# BaseNode.net
KiCad netlist of a schematic drawn in Altium Designer
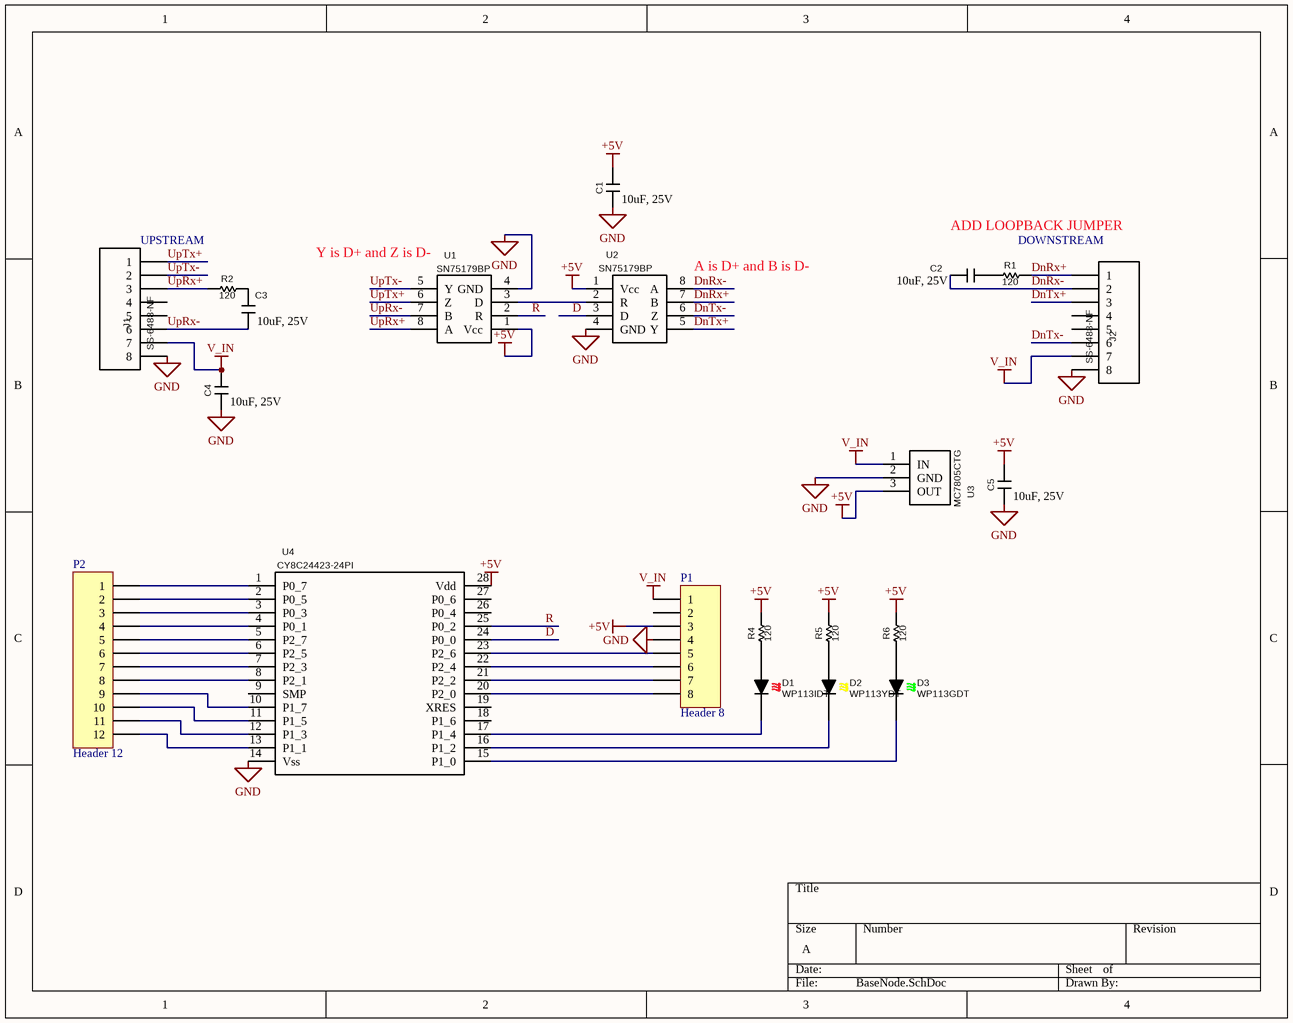
[diagram p0: BaseNode.SchDoc]

(export (version "E")
  (design (tool "Eeschema 10.0.6"))
  (components
    (comp (ref "C1")
      (value "10uF, 25V")
      (footprint "whong:Capacitor TH 0.2")
      (description "Capacitor")
      (fields (field (name "MANUFACTURER") "TDK Corporation"))
      (libsource (lib "whong") (part "Capacitor"))
    )
    (comp (ref "C2")
      (value "10uF, 25V")
      (footprint "whong:Capacitor TH 0.2")
      (description "Capacitor")
      (fields (field (name "MANUFACTURER") "TDK Corporation"))
      (libsource (lib "whong") (part "Capacitor"))
    )
    (comp (ref "C3")
      (value "10uF, 25V")
      (footprint "whong:Capacitor TH 0.2")
      (description "Capacitor")
      (fields (field (name "MANUFACTURER") "TDK Corporation"))
      (libsource (lib "whong") (part "Capacitor"))
    )
    (comp (ref "C4")
      (value "10uF, 25V")
      (footprint "whong:Capacitor TH 0.2")
      (description "Capacitor")
      (fields (field (name "MANUFACTURER") "TDK Corporation"))
      (libsource (lib "whong") (part "Capacitor"))
    )
    (comp (ref "C5")
      (value "10uF, 25V")
      (footprint "whong:Capacitor TH 0.2")
      (description "Capacitor")
      (fields (field (name "MANUFACTURER") "TDK Corporation"))
      (libsource (lib "whong") (part "Capacitor"))
    )
    (comp (ref "D1")
      (value "WP113IDT")
      (footprint "whong:LED 100mil")
      (description "LED RECT 2X5MM 625NM RED DIFF")
      (fields (field (name "MANUFACTURER") "Kingbright Corp") (field (name "MANUFACTURERPN") "WP113IDT"))
      (libsource (lib "whong") (part "WP113IDT"))
    )
    (comp (ref "D2")
      (value "WP113YDT")
      (footprint "whong:LED 100mil")
      (description "LED RECT 2X5MM 588NM YLW DIFF")
      (fields (field (name "MANUFACTURER") "Kingbright Corp") (field (name "MANUFACTURERPN") "WP113YDT"))
      (libsource (lib "whong") (part "WP113YDT"))
    )
    (comp (ref "D3")
      (value "WP113GDT")
      (footprint "whong:LED 100mil")
      (description "LED RECT 2X5MM 568NM GRN DIFF")
      (fields (field (name "MANUFACTURER") "Kingbright Corp") (field (name "MANUFACTURERPN") "WP113GDT"))
      (libsource (lib "whong") (part "WP113GDT"))
    )
    (comp (ref "J1")
      (value "SS-6488-NF")
      (footprint "whong:SS-6488-NF")
      (description "CONN 8-8 MOD JACK")
      (fields (field (name "MANUFACTURER") "Stewart Connector"))
      (libsource (lib "") (part "SS-6488-NF_1"))
    )
    (comp (ref "J2")
      (value "SS-6488-NF")
      (footprint "whong:SS-6488-NF")
      (description "CONN 8-8 MOD JACK")
      (fields (field (name "MANUFACTURER") "Stewart Connector"))
      (libsource (lib "whong") (part "SS-6488-NF"))
    )
    (comp (ref "P1")
      (value "Header 8")
      (footprint "HDR1X8")
      (description "Header, 8-Pin")
      (fields (field (name "PUBLISHER") "Altium Limited"))
      (libsource (lib "Miscellaneous Connectors") (part "Header 8"))
    )
    (comp (ref "P2")
      (value "Header 12")
      (footprint "HDR1X12")
      (description "Header, 12-Pin")
      (fields (field (name "PUBLISHER") "Altium Limited"))
      (libsource (lib "Miscellaneous Connectors") (part "Header 12"))
    )
    (comp (ref "R1")
      (value "120")
      (footprint "whong:Resistor Axial 100mil")
      (description "Resistor")
      (fields (field (name "MANUFACTURER") "Stackpole Electronics Inc") (field (name "TOLERANCE") "5%"))
      (libsource (lib "whong") (part "Resistor"))
    )
    (comp (ref "R2")
      (value "120")
      (footprint "whong:Resistor Axial 100mil")
      (description "Resistor")
      (fields (field (name "MANUFACTURER") "Stackpole Electronics Inc") (field (name "TOLERANCE") "5%"))
      (libsource (lib "whong") (part "Resistor"))
    )
    (comp (ref "R4")
      (value "120")
      (footprint "whong:Resistor Axial 100mil")
      (description "Resistor")
      (fields (field (name "MANUFACTURER") "Stackpole Electronics Inc") (field (name "TOLERANCE") "5%"))
      (libsource (lib "whong") (part "Resistor"))
    )
    (comp (ref "R5")
      (value "120")
      (footprint "whong:Resistor Axial 100mil")
      (description "Resistor")
      (fields (field (name "MANUFACTURER") "Stackpole Electronics Inc") (field (name "TOLERANCE") "5%"))
      (libsource (lib "whong") (part "Resistor"))
    )
    (comp (ref "R6")
      (value "120")
      (footprint "whong:Resistor Axial 100mil")
      (description "Resistor")
      (fields (field (name "MANUFACTURER") "Stackpole Electronics Inc") (field (name "TOLERANCE") "5%"))
      (libsource (lib "whong") (part "Resistor"))
    )
    (comp (ref "U1")
      (value "SN75179BP")
      (footprint "dip8")
      (description "IC DIFF DRIVER/RECPAIR 8-DIP")
      (fields (field (name "MANUFACTURER") "Texas Instruments"))
      (libsource (lib "") (part "SN75179BP_1"))
    )
    (comp (ref "U2")
      (value "SN75179BP")
      (footprint "dip8")
      (description "IC DIFF DRIVER/RECPAIR 8-DIP")
      (fields (field (name "MANUFACTURER") "Texas Instruments"))
      (libsource (lib "whong") (part "SN75179BP"))
    )
    (comp (ref "U3")
      (value "MC7805CTG")
      (footprint "whong:TO-220")
      (description "IC REG VOLT POS 1A 5V TO220AB")
      (fields (field (name "MANUFACTURER") "ON Semiconductor"))
      (libsource (lib "whong") (part "MC7805CTG"))
    )
    (comp (ref "U4")
      (value "CY8C24423-24PI")
      (footprint "dip28")
      (description "IC MCU 4K FLASH 256B 28-DIP")
      (fields (field (name "MANUFACTURER") "Cypress Semiconductor Corp"))
      (libsource (lib "whong") (part "CY8C24423-24PI"))
    )
  )
  (nets
    (net (code "1") (name "+5V") (class "Default")
      (node (ref "C1") (pin "2") (pinfunction "2_2") (pintype "passive"))
      (node (ref "C5") (pin "2") (pinfunction "2_2") (pintype "passive"))
      (node (ref "P1") (pin "3") (pinfunction "3_3") (pintype "passive"))
      (node (ref "R4") (pin "2") (pinfunction "2_2") (pintype "passive"))
      (node (ref "R5") (pin "2") (pinfunction "2_2") (pintype "passive"))
      (node (ref "R6") (pin "2") (pinfunction "2_2") (pintype "passive"))
      (node (ref "U1") (pin "1") (pinfunction "Vcc_1") (pintype "passive"))
      (node (ref "U2") (pin "1") (pinfunction "Vcc_1") (pintype "passive"))
      (node (ref "U3") (pin "3") (pinfunction "OUT_3") (pintype "passive"))
      (node (ref "U4") (pin "28") (pinfunction "Vdd_28") (pintype "passive"))
    )
    (net (code "2") (name "/D") (class "Default")
      (node (ref "U2") (pin "3") (pinfunction "D_3") (pintype "passive"))
      (node (ref "U4") (pin "24") (pinfunction "P0_0_24") (pintype "passive"))
    )
    (net (code "3") (name "/DnRx+") (class "Default")
      (node (ref "J2") (pin "1") (pinfunction "1_1") (pintype "passive"))
      (node (ref "R1") (pin "2") (pinfunction "2_2") (pintype "passive"))
      (node (ref "U2") (pin "7") (pinfunction "B_7") (pintype "passive"))
    )
    (net (code "4") (name "/DnRx-") (class "Default")
      (node (ref "C2") (pin "2") (pinfunction "2_2") (pintype "passive"))
      (node (ref "J2") (pin "2") (pinfunction "2_2") (pintype "passive"))
      (node (ref "U2") (pin "8") (pinfunction "A_8") (pintype "passive"))
    )
    (net (code "5") (name "/DnTx+") (class "Default")
      (node (ref "J2") (pin "3") (pinfunction "3_3") (pintype "passive"))
      (node (ref "U2") (pin "5") (pinfunction "Y_5") (pintype "passive"))
    )
    (net (code "6") (name "/DnTx-") (class "Default")
      (node (ref "J2") (pin "6") (pinfunction "6_6") (pintype "passive"))
      (node (ref "U2") (pin "6") (pinfunction "Z_6") (pintype "passive"))
    )
    (net (code "7") (name "/R") (class "Default")
      (node (ref "U1") (pin "2") (pinfunction "R_2") (pintype "passive"))
      (node (ref "U4") (pin "25") (pinfunction "P0_2_25") (pintype "passive"))
    )
    (net (code "8") (name "/UpRx+") (class "Default")
      (node (ref "J1") (pin "3") (pinfunction "3_3") (pintype "passive"))
      (node (ref "R2") (pin "1") (pinfunction "1_1") (pintype "passive"))
      (node (ref "U1") (pin "8") (pinfunction "A_8") (pintype "passive"))
    )
    (net (code "9") (name "/UpRx-") (class "Default")
      (node (ref "C3") (pin "1") (pinfunction "1_1") (pintype "passive"))
      (node (ref "J1") (pin "6") (pinfunction "6_6") (pintype "passive"))
      (node (ref "U1") (pin "7") (pinfunction "B_7") (pintype "passive"))
    )
    (net (code "10") (name "/UpTx+") (class "Default")
      (node (ref "J1") (pin "1") (pinfunction "1_1") (pintype "passive"))
      (node (ref "U1") (pin "6") (pinfunction "Z_6") (pintype "passive"))
    )
    (net (code "11") (name "/UpTx-") (class "Default")
      (node (ref "J1") (pin "2") (pinfunction "2_2") (pintype "passive"))
      (node (ref "U1") (pin "5") (pinfunction "Y_5") (pintype "passive"))
    )
    (net (code "12") (name "GND") (class "Default")
      (node (ref "C1") (pin "1") (pinfunction "1_1") (pintype "passive"))
      (node (ref "C4") (pin "1") (pinfunction "1_1") (pintype "passive"))
      (node (ref "C5") (pin "1") (pinfunction "1_1") (pintype "passive"))
      (node (ref "J1") (pin "8") (pinfunction "8_8") (pintype "passive"))
      (node (ref "J2") (pin "8") (pinfunction "8_8") (pintype "passive"))
      (node (ref "P1") (pin "4") (pinfunction "4_4") (pintype "passive"))
      (node (ref "U1") (pin "4") (pinfunction "GND_4") (pintype "passive"))
      (node (ref "U2") (pin "4") (pinfunction "GND_4") (pintype "passive"))
      (node (ref "U3") (pin "2") (pinfunction "GND_2") (pintype "passive"))
      (node (ref "U4") (pin "14") (pinfunction "Vss_14") (pintype "passive"))
    )
    (net (code "13") (name "Net-(C2-Pad1)") (class "Default")
      (node (ref "C2") (pin "1") (pinfunction "1_1") (pintype "passive"))
      (node (ref "R1") (pin "1") (pinfunction "1_1") (pintype "passive"))
    )
    (net (code "14") (name "Net-(C3-Pad2)") (class "Default")
      (node (ref "C3") (pin "2") (pinfunction "2_2") (pintype "passive"))
      (node (ref "R2") (pin "2") (pinfunction "2_2") (pintype "passive"))
    )
    (net (code "15") (name "Net-(D1-PadA)") (class "Default")
      (node (ref "D1") (pin "A") (pinfunction "A_A") (pintype "passive"))
      (node (ref "R4") (pin "1") (pinfunction "1_1") (pintype "passive"))
    )
    (net (code "16") (name "Net-(D2-PadA)") (class "Default")
      (node (ref "D2") (pin "A") (pinfunction "A_A") (pintype "passive"))
      (node (ref "R5") (pin "1") (pinfunction "1_1") (pintype "passive"))
    )
    (net (code "17") (name "Net-(D3-PadA)") (class "Default")
      (node (ref "D3") (pin "A") (pinfunction "A_A") (pintype "passive"))
      (node (ref "R6") (pin "1") (pinfunction "1_1") (pintype "passive"))
    )
    (net (code "18") (name "Net-(U1-D)") (class "Default")
      (node (ref "U1") (pin "3") (pinfunction "D_3") (pintype "passive"))
      (node (ref "U2") (pin "2") (pinfunction "R_2") (pintype "passive"))
    )
    (net (code "19") (name "Net-(U4-P0_1)") (class "Default")
      (node (ref "P2") (pin "4") (pinfunction "4_4") (pintype "passive"))
      (node (ref "U4") (pin "4") (pinfunction "P0_1_4") (pintype "passive"))
    )
    (net (code "20") (name "Net-(U4-P0_3)") (class "Default")
      (node (ref "P2") (pin "3") (pinfunction "3_3") (pintype "passive"))
      (node (ref "U4") (pin "3") (pinfunction "P0_3_3") (pintype "passive"))
    )
    (net (code "21") (name "Net-(U4-P0_5)") (class "Default")
      (node (ref "P2") (pin "2") (pinfunction "2_2") (pintype "passive"))
      (node (ref "U4") (pin "2") (pinfunction "P0_5_2") (pintype "passive"))
    )
    (net (code "22") (name "Net-(U4-P0_7)") (class "Default")
      (node (ref "P2") (pin "1") (pinfunction "1_1") (pintype "passive"))
      (node (ref "U4") (pin "1") (pinfunction "P0_7_1") (pintype "passive"))
    )
    (net (code "23") (name "Net-(U4-P1_0)") (class "Default")
      (node (ref "D3") (pin "K") (pinfunction "K_K") (pintype "passive"))
      (node (ref "U4") (pin "15") (pinfunction "P1_0_15") (pintype "passive"))
    )
    (net (code "24") (name "Net-(U4-P1_1)") (class "Default")
      (node (ref "P2") (pin "12") (pinfunction "12_12") (pintype "passive"))
      (node (ref "U4") (pin "13") (pinfunction "P1_1_13") (pintype "passive"))
    )
    (net (code "25") (name "Net-(U4-P1_2)") (class "Default")
      (node (ref "D2") (pin "K") (pinfunction "K_K") (pintype "passive"))
      (node (ref "U4") (pin "16") (pinfunction "P1_2_16") (pintype "passive"))
    )
    (net (code "26") (name "Net-(U4-P1_3)") (class "Default")
      (node (ref "P2") (pin "11") (pinfunction "11_11") (pintype "passive"))
      (node (ref "U4") (pin "12") (pinfunction "P1_3_12") (pintype "passive"))
    )
    (net (code "27") (name "Net-(U4-P1_4)") (class "Default")
      (node (ref "D1") (pin "K") (pinfunction "K_K") (pintype "passive"))
      (node (ref "U4") (pin "17") (pinfunction "P1_4_17") (pintype "passive"))
    )
    (net (code "28") (name "Net-(U4-P1_5)") (class "Default")
      (node (ref "P2") (pin "10") (pinfunction "10_10") (pintype "passive"))
      (node (ref "U4") (pin "11") (pinfunction "P1_5_11") (pintype "passive"))
    )
    (net (code "29") (name "Net-(U4-P1_7)") (class "Default")
      (node (ref "P2") (pin "9") (pinfunction "9_9") (pintype "passive"))
      (node (ref "U4") (pin "10") (pinfunction "P1_7_10") (pintype "passive"))
    )
    (net (code "30") (name "Net-(U4-P2_0)") (class "Default")
      (node (ref "P1") (pin "8") (pinfunction "8_8") (pintype "passive"))
      (node (ref "U4") (pin "20") (pinfunction "P2_0_20") (pintype "passive"))
    )
    (net (code "31") (name "Net-(U4-P2_1)") (class "Default")
      (node (ref "P2") (pin "8") (pinfunction "8_8") (pintype "passive"))
      (node (ref "U4") (pin "8") (pinfunction "P2_1_8") (pintype "passive"))
    )
    (net (code "32") (name "Net-(U4-P2_2)") (class "Default")
      (node (ref "P1") (pin "7") (pinfunction "7_7") (pintype "passive"))
      (node (ref "U4") (pin "21") (pinfunction "P2_2_21") (pintype "passive"))
    )
    (net (code "33") (name "Net-(U4-P2_3)") (class "Default")
      (node (ref "P2") (pin "7") (pinfunction "7_7") (pintype "passive"))
      (node (ref "U4") (pin "7") (pinfunction "P2_3_7") (pintype "passive"))
    )
    (net (code "34") (name "Net-(U4-P2_4)") (class "Default")
      (node (ref "P1") (pin "6") (pinfunction "6_6") (pintype "passive"))
      (node (ref "U4") (pin "22") (pinfunction "P2_4_22") (pintype "passive"))
    )
    (net (code "35") (name "Net-(U4-P2_5)") (class "Default")
      (node (ref "P2") (pin "6") (pinfunction "6_6") (pintype "passive"))
      (node (ref "U4") (pin "6") (pinfunction "P2_5_6") (pintype "passive"))
    )
    (net (code "36") (name "Net-(U4-P2_6)") (class "Default")
      (node (ref "P1") (pin "5") (pinfunction "5_5") (pintype "passive"))
      (node (ref "U4") (pin "23") (pinfunction "P2_6_23") (pintype "passive"))
    )
    (net (code "37") (name "Net-(U4-P2_7)") (class "Default")
      (node (ref "P2") (pin "5") (pinfunction "5_5") (pintype "passive"))
      (node (ref "U4") (pin "5") (pinfunction "P2_7_5") (pintype "passive"))
    )
    (net (code "38") (name "V_IN") (class "Default")
      (node (ref "C4") (pin "2") (pinfunction "2_2") (pintype "passive"))
      (node (ref "J1") (pin "7") (pinfunction "7_7") (pintype "passive"))
      (node (ref "J2") (pin "7") (pinfunction "7_7") (pintype "passive"))
      (node (ref "P1") (pin "1") (pinfunction "1_1") (pintype "passive"))
      (node (ref "U3") (pin "1") (pinfunction "IN_1") (pintype "passive"))
    )
    (net (code "39") (name "unconnected-(J1-Pad4)") (class "Default")
      (node (ref "J1") (pin "4") (pinfunction "4_4") (pintype "passive"))
    )
    (net (code "40") (name "unconnected-(J1-Pad5)") (class "Default")
      (node (ref "J1") (pin "5") (pinfunction "5_5") (pintype "passive"))
    )
    (net (code "41") (name "unconnected-(J2-Pad4)") (class "Default")
      (node (ref "J2") (pin "4") (pinfunction "4_4") (pintype "passive"))
    )
    (net (code "42") (name "unconnected-(J2-Pad5)") (class "Default")
      (node (ref "J2") (pin "5") (pinfunction "5_5") (pintype "passive"))
    )
    (net (code "43") (name "unconnected-(P1-Pad2)") (class "Default")
      (node (ref "P1") (pin "2") (pinfunction "2_2") (pintype "passive"))
    )
    (net (code "44") (name "unconnected-(U4-P0_4-Pad26)") (class "Default")
      (node (ref "U4") (pin "26") (pinfunction "P0_4_26") (pintype "passive"))
    )
    (net (code "45") (name "unconnected-(U4-P0_6-Pad27)") (class "Default")
      (node (ref "U4") (pin "27") (pinfunction "P0_6_27") (pintype "passive"))
    )
    (net (code "46") (name "unconnected-(U4-P1_6-Pad18)") (class "Default")
      (node (ref "U4") (pin "18") (pinfunction "P1_6_18") (pintype "passive"))
    )
    (net (code "47") (name "unconnected-(U4-SMP-Pad9)") (class "Default")
      (node (ref "U4") (pin "9") (pinfunction "SMP_9") (pintype "passive"))
    )
    (net (code "48") (name "unconnected-(U4-XRES-Pad19)") (class "Default")
      (node (ref "U4") (pin "19") (pinfunction "XRES_19") (pintype "passive"))
    )
  )
)
